# Xplorer_camera.net
KiCad netlist of a schematic drawn in Altium Designer
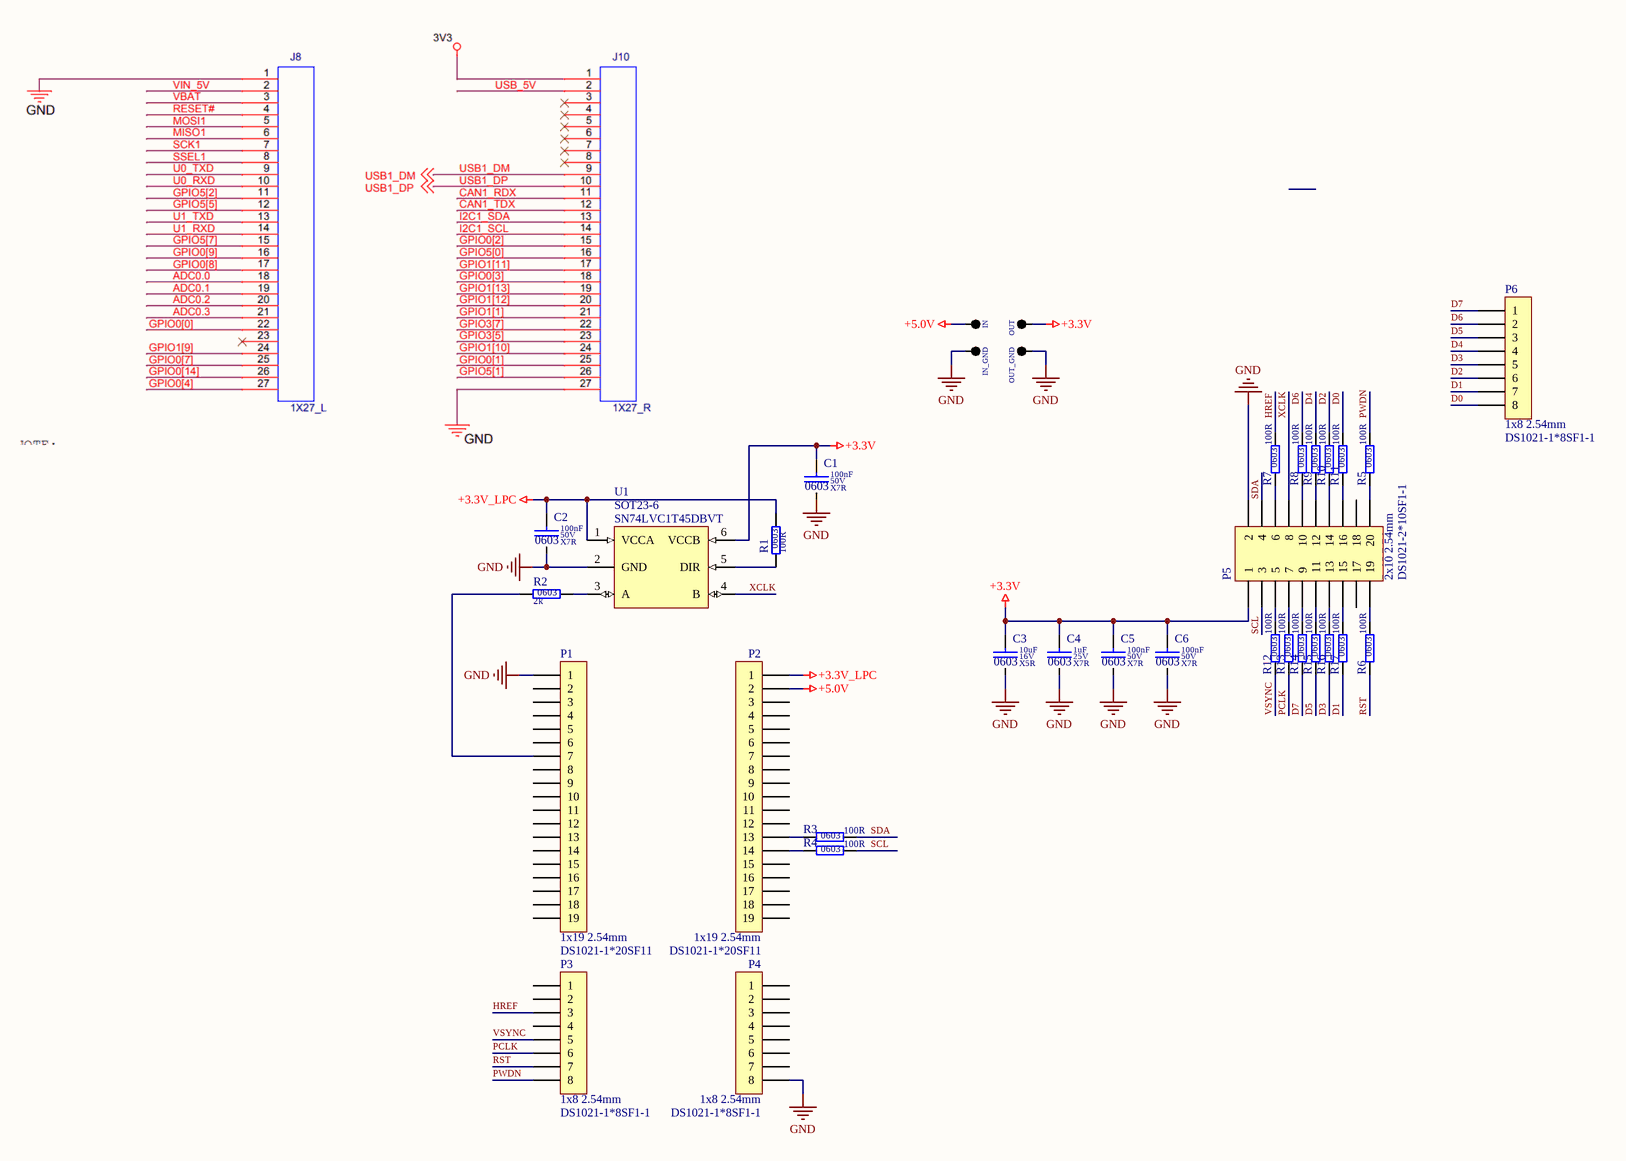
[diagram p0: Xplorer_camera.SchDoc]

(export (version "E")
  (design (tool "Eeschema 10.0.6"))
  (components
    (comp (ref "C1")
      (value "100nF")
      (footprint "C_0603_1608")
      (description "Capacitor")
      (fields
        (field (name "DIELECTRIC") "X7R")
        (field (name "VOLTAGE") "50V")
        (field (name "SCH_FOOTPRINT") "0603")
        (field (name "PART NUMBER") "C_100nF_50V_X7R_0603_5")
        (field (name "MANUFACTURER") "Samsung")
      )
      (libsource (lib "Library") (part "C"))
    )
    (comp (ref "C2")
      (value "100nF")
      (footprint "C_0603_1608")
      (description "Capacitor")
      (fields
        (field (name "DIELECTRIC") "X7R")
        (field (name "VOLTAGE") "50V")
        (field (name "SCH_FOOTPRINT") "0603")
        (field (name "PART NUMBER") "C_100nF_50V_X7R_0603_5")
        (field (name "MANUFACTURER") "Samsung")
      )
      (libsource (lib "Library") (part "C"))
    )
    (comp (ref "C3")
      (value "10uF")
      (footprint "C_0603_1608")
      (description "Capacitor")
      (fields
        (field (name "DIELECTRIC") "X5R")
        (field (name "VOLTAGE") "16V")
        (field (name "SCH_FOOTPRINT") "0603")
        (field (name "PART NUMBER") "C_10uF_16V_X5R_0603_20")
        (field (name "MANUFACTURER") "Samsung Electro-Mechanics")
      )
      (libsource (lib "Library") (part "C"))
    )
    (comp (ref "C4")
      (value "1uF")
      (footprint "C_0603_1608")
      (description "Capacitor")
      (fields
        (field (name "DIELECTRIC") "X7R")
        (field (name "VOLTAGE") "25V")
        (field (name "SCH_FOOTPRINT") "0603")
        (field (name "PART NUMBER") "C_1uF_25V_X7R_0603_10")
        (field (name "MANUFACTURER") "Samsung")
      )
      (libsource (lib "Library") (part "C"))
    )
    (comp (ref "C5")
      (value "100nF")
      (footprint "C_0603_1608")
      (description "Capacitor")
      (fields
        (field (name "DIELECTRIC") "X7R")
        (field (name "VOLTAGE") "50V")
        (field (name "SCH_FOOTPRINT") "0603")
        (field (name "PART NUMBER") "C_100nF_50V_X7R_0603_5")
        (field (name "MANUFACTURER") "Samsung")
      )
      (libsource (lib "Library") (part "C"))
    )
    (comp (ref "C6")
      (value "100nF")
      (footprint "C_0603_1608")
      (description "Capacitor")
      (fields
        (field (name "DIELECTRIC") "X7R")
        (field (name "VOLTAGE") "50V")
        (field (name "SCH_FOOTPRINT") "0603")
        (field (name "PART NUMBER") "C_100nF_50V_X7R_0603_5")
        (field (name "MANUFACTURER") "Samsung")
      )
      (libsource (lib "Library") (part "C"))
    )
    (comp (ref "IN")
      (value "Single pin")
      (footprint "TP_1PIN")
      (description "Testpoint")
      (fields (field (name "PART NUMBER") "TP_1PIN"))
      (libsource (lib "Library") (part "TP_TESTPOINT"))
    )
    (comp (ref "IN_GND")
      (value "Single pin")
      (footprint "TP_1PIN")
      (description "Testpoint")
      (fields (field (name "PART NUMBER") "TP_1PIN"))
      (libsource (lib "Library") (part "TP_TESTPOINT"))
    )
    (comp (ref "OUT")
      (value "Single pin")
      (footprint "TP_1PIN")
      (description "Testpoint")
      (fields (field (name "PART NUMBER") "TP_1PIN"))
      (libsource (lib "Library") (part "TP_TESTPOINT"))
    )
    (comp (ref "OUT_GND")
      (value "Single pin")
      (footprint "TP_1PIN")
      (description "Testpoint")
      (fields (field (name "PART NUMBER") "TP_1PIN"))
      (libsource (lib "Library") (part "TP_TESTPOINT"))
    )
    (comp (ref "P1")
      (value "DS1021-1*20SF11")
      (footprint "P_HEADER_1x19_2.54")
      (description "Pin Header")
      (fields
        (field (name "SCH_FOOTPRINT") "1x19 2.54mm")
        (field (name "PART NUMBER") "P_HEADER_1x19_2.54")
        (field (name "MANUFACTURER") "Connfly")
      )
      (libsource (lib "") (part "P_HEADER_1x19_1"))
    )
    (comp (ref "P2")
      (value "DS1021-1*20SF11")
      (footprint "P_HEADER_1x19_2.54")
      (description "Pin Header")
      (fields
        (field (name "SCH_FOOTPRINT") "1x19 2.54mm")
        (field (name "PART NUMBER") "P_HEADER_1x19_2.54")
        (field (name "MANUFACTURER") "Connfly")
      )
      (libsource (lib "Library") (part "P_HEADER_1x19"))
    )
    (comp (ref "P3")
      (value "DS1021-1*8SF1-1")
      (footprint "P_HEADER_1x8_2.54")
      (description "Pin Header")
      (fields
        (field (name "SCH_FOOTPRINT") "1x8 2.54mm")
        (field (name "PART NUMBER") "P_HEADER_1x8_2.54")
        (field (name "MANUFACTURER") "Connfly")
      )
      (libsource (lib "Library") (part "P_HEADER_1x8"))
    )
    (comp (ref "P4")
      (value "DS1021-1*8SF1-1")
      (footprint "P_HEADER_1x8_2.54")
      (description "Pin Header")
      (fields
        (field (name "SCH_FOOTPRINT") "1x8 2.54mm")
        (field (name "PART NUMBER") "P_HEADER_1x8_2.54")
        (field (name "MANUFACTURER") "Connfly")
      )
      (libsource (lib "") (part "P_HEADER_1x8_1"))
    )
    (comp (ref "P5")
      (value "DS1021-2*10SF1-1")
      (footprint "P_HEADER_2x10_2.54")
      (description "Pin Header")
      (fields
        (field (name "SCH_FOOTPRINT") "2x10 2.54mm")
        (field (name "PART NUMBER") "P_HEADER_2x10_2.54")
        (field (name "MANUFACTURER") "Connfly")
      )
      (libsource (lib "Library") (part "P_HEADER_2x10"))
    )
    (comp (ref "P6")
      (value "DS1021-1*8SF1-1")
      (footprint "P_HEADER_1x8_2.54")
      (description "Pin Header")
      (fields
        (field (name "SCH_FOOTPRINT") "1x8 2.54mm")
        (field (name "PART NUMBER") "P_HEADER_1x8_2.54")
        (field (name "MANUFACTURER") "Connfly")
      )
      (libsource (lib "Library") (part "P_HEADER_1x8"))
    )
    (comp (ref "R1")
      (value "100R")
      (footprint "R_0603_1608")
      (fields
        (field (name "SCH_FOOTPRINT") "0603")
        (field (name "PART NUMBER") "R_100R_0603_1")
        (field (name "VOLTAGE") "50V")
        (field (name "POWER") "100mW")
      )
      (libsource (lib "Library") (part "R"))
    )
    (comp (ref "R2")
      (value "2k")
      (footprint "R_0603_1608")
      (fields
        (field (name "SCH_FOOTPRINT") "0603")
        (field (name "PART NUMBER") "R_2k_0603_1")
        (field (name "VOLTAGE") "50V")
        (field (name "POWER") "100mW")
      )
      (libsource (lib "Library") (part "R"))
    )
    (comp (ref "R3")
      (value "100R")
      (footprint "R_0603_1608")
      (fields
        (field (name "SCH_FOOTPRINT") "0603")
        (field (name "PART NUMBER") "R_100R_0603_1")
        (field (name "VOLTAGE") "50V")
        (field (name "POWER") "100mW")
      )
      (libsource (lib "Library") (part "R"))
    )
    (comp (ref "R4")
      (value "100R")
      (footprint "R_0603_1608")
      (fields
        (field (name "SCH_FOOTPRINT") "0603")
        (field (name "PART NUMBER") "R_100R_0603_1")
        (field (name "VOLTAGE") "50V")
        (field (name "POWER") "100mW")
      )
      (libsource (lib "Library") (part "R"))
    )
    (comp (ref "R5")
      (value "100R")
      (footprint "R_0603_1608")
      (fields
        (field (name "SCH_FOOTPRINT") "0603")
        (field (name "PART NUMBER") "R_100R_0603_1")
        (field (name "VOLTAGE") "50V")
        (field (name "POWER") "100mW")
      )
      (libsource (lib "Library") (part "R"))
    )
    (comp (ref "R6")
      (value "100R")
      (footprint "R_0603_1608")
      (fields
        (field (name "SCH_FOOTPRINT") "0603")
        (field (name "PART NUMBER") "R_100R_0603_1")
        (field (name "VOLTAGE") "50V")
        (field (name "POWER") "100mW")
      )
      (libsource (lib "Library") (part "R"))
    )
    (comp (ref "R7")
      (value "100R")
      (footprint "R_0603_1608")
      (fields
        (field (name "SCH_FOOTPRINT") "0603")
        (field (name "PART NUMBER") "R_100R_0603_1")
        (field (name "VOLTAGE") "50V")
        (field (name "POWER") "100mW")
      )
      (libsource (lib "Library") (part "R"))
    )
    (comp (ref "R8")
      (value "100R")
      (footprint "R_0603_1608")
      (fields
        (field (name "SCH_FOOTPRINT") "0603")
        (field (name "PART NUMBER") "R_100R_0603_1")
        (field (name "VOLTAGE") "50V")
        (field (name "POWER") "100mW")
      )
      (libsource (lib "Library") (part "R"))
    )
    (comp (ref "R9")
      (value "100R")
      (footprint "R_0603_1608")
      (fields
        (field (name "SCH_FOOTPRINT") "0603")
        (field (name "PART NUMBER") "R_100R_0603_1")
        (field (name "VOLTAGE") "50V")
        (field (name "POWER") "100mW")
      )
      (libsource (lib "Library") (part "R"))
    )
    (comp (ref "R10")
      (value "100R")
      (footprint "R_0603_1608")
      (fields
        (field (name "SCH_FOOTPRINT") "0603")
        (field (name "PART NUMBER") "R_100R_0603_1")
        (field (name "VOLTAGE") "50V")
        (field (name "POWER") "100mW")
      )
      (libsource (lib "Library") (part "R"))
    )
    (comp (ref "R11")
      (value "100R")
      (footprint "R_0603_1608")
      (fields
        (field (name "SCH_FOOTPRINT") "0603")
        (field (name "PART NUMBER") "R_100R_0603_1")
        (field (name "VOLTAGE") "50V")
        (field (name "POWER") "100mW")
      )
      (libsource (lib "Library") (part "R"))
    )
    (comp (ref "R12")
      (value "100R")
      (footprint "R_0603_1608")
      (fields
        (field (name "SCH_FOOTPRINT") "0603")
        (field (name "PART NUMBER") "R_100R_0603_1")
        (field (name "VOLTAGE") "50V")
        (field (name "POWER") "100mW")
      )
      (libsource (lib "Library") (part "R"))
    )
    (comp (ref "R13")
      (value "100R")
      (footprint "R_0603_1608")
      (fields
        (field (name "SCH_FOOTPRINT") "0603")
        (field (name "PART NUMBER") "R_100R_0603_1")
        (field (name "VOLTAGE") "50V")
        (field (name "POWER") "100mW")
      )
      (libsource (lib "Library") (part "R"))
    )
    (comp (ref "R14")
      (value "100R")
      (footprint "R_0603_1608")
      (fields
        (field (name "SCH_FOOTPRINT") "0603")
        (field (name "PART NUMBER") "R_100R_0603_1")
        (field (name "VOLTAGE") "50V")
        (field (name "POWER") "100mW")
      )
      (libsource (lib "Library") (part "R"))
    )
    (comp (ref "R15")
      (value "100R")
      (footprint "R_0603_1608")
      (fields
        (field (name "SCH_FOOTPRINT") "0603")
        (field (name "PART NUMBER") "R_100R_0603_1")
        (field (name "VOLTAGE") "50V")
        (field (name "POWER") "100mW")
      )
      (libsource (lib "Library") (part "R"))
    )
    (comp (ref "R16")
      (value "100R")
      (footprint "R_0603_1608")
      (fields
        (field (name "SCH_FOOTPRINT") "0603")
        (field (name "PART NUMBER") "R_100R_0603_1")
        (field (name "VOLTAGE") "50V")
        (field (name "POWER") "100mW")
      )
      (libsource (lib "Library") (part "R"))
    )
    (comp (ref "R17")
      (value "100R")
      (footprint "R_0603_1608")
      (fields
        (field (name "SCH_FOOTPRINT") "0603")
        (field (name "PART NUMBER") "R_100R_0603_1")
        (field (name "VOLTAGE") "50V")
        (field (name "POWER") "100mW")
      )
      (libsource (lib "Library") (part "R"))
    )
    (comp (ref "U1")
      (value "SN74LVC1T45DBVT")
      (footprint "SOT23-6_SC74A_SOT753")
      (fields
        (field (name "SCH_FOOTPRINT") "SOT23-6")
        (field (name "PART NUMBER") "U_SN74LVC1T45DBVT")
        (field (name "MANUFACTURER") "Texas Instruments")
        (field (name "Comment") "Single-Bit Dual-Supply Bus Transceiver")
      )
      (libsource (lib "Library") (part "U_SN74LVC1T45"))
    )
  )
  (nets
    (net (code "1") (name "+3.3V") (class "Default")
      (node (ref "C1") (pin "1") (pinfunction "1_1") (pintype "passive"))
      (node (ref "C3") (pin "1") (pinfunction "1_1") (pintype "passive"))
      (node (ref "C4") (pin "1") (pinfunction "1_1") (pintype "passive"))
      (node (ref "C5") (pin "1") (pinfunction "1_1") (pintype "passive"))
      (node (ref "C6") (pin "1") (pinfunction "1_1") (pintype "passive"))
      (node (ref "OUT") (pin "1") (pinfunction "TP_1") (pintype "passive"))
      (node (ref "P5") (pin "1") (pinfunction "1_1") (pintype "passive"))
      (node (ref "U1") (pin "6") (pinfunction "VCCB_6") (pintype "input"))
    )
    (net (code "2") (name "+3.3V_LPC") (class "Default")
      (node (ref "C2") (pin "1") (pinfunction "1_1") (pintype "passive"))
      (node (ref "P2") (pin "1") (pinfunction "1_1") (pintype "passive"))
      (node (ref "R1") (pin "2") (pinfunction "2_2") (pintype "passive"))
      (node (ref "U1") (pin "1") (pinfunction "VCCA_1") (pintype "input"))
    )
    (net (code "3") (name "+5.0V") (class "Default")
      (node (ref "IN") (pin "1") (pinfunction "TP_1") (pintype "passive"))
      (node (ref "P2") (pin "2") (pinfunction "2_2") (pintype "passive"))
    )
    (net (code "4") (name "/D0") (class "Default")
      (node (ref "P6") (pin "8") (pinfunction "8_8") (pintype "passive"))
      (node (ref "R11") (pin "2") (pinfunction "2_2") (pintype "passive"))
    )
    (net (code "5") (name "/D1") (class "Default")
      (node (ref "P6") (pin "7") (pinfunction "7_7") (pintype "passive"))
      (node (ref "R17") (pin "1") (pinfunction "1_1") (pintype "passive"))
    )
    (net (code "6") (name "/D2") (class "Default")
      (node (ref "P6") (pin "6") (pinfunction "6_6") (pintype "passive"))
      (node (ref "R10") (pin "2") (pinfunction "2_2") (pintype "passive"))
    )
    (net (code "7") (name "/D3") (class "Default")
      (node (ref "P6") (pin "5") (pinfunction "5_5") (pintype "passive"))
      (node (ref "R16") (pin "1") (pinfunction "1_1") (pintype "passive"))
    )
    (net (code "8") (name "/D4") (class "Default")
      (node (ref "P6") (pin "4") (pinfunction "4_4") (pintype "passive"))
      (node (ref "R9") (pin "2") (pinfunction "2_2") (pintype "passive"))
    )
    (net (code "9") (name "/D5") (class "Default")
      (node (ref "P6") (pin "3") (pinfunction "3_3") (pintype "passive"))
      (node (ref "R15") (pin "1") (pinfunction "1_1") (pintype "passive"))
    )
    (net (code "10") (name "/D6") (class "Default")
      (node (ref "P6") (pin "2") (pinfunction "2_2") (pintype "passive"))
      (node (ref "R8") (pin "2") (pinfunction "2_2") (pintype "passive"))
    )
    (net (code "11") (name "/D7") (class "Default")
      (node (ref "P6") (pin "1") (pinfunction "1_1") (pintype "passive"))
      (node (ref "R14") (pin "1") (pinfunction "1_1") (pintype "passive"))
    )
    (net (code "12") (name "/HREF") (class "Default")
      (node (ref "P3") (pin "3") (pinfunction "3_3") (pintype "passive"))
      (node (ref "R7") (pin "2") (pinfunction "2_2") (pintype "passive"))
    )
    (net (code "13") (name "/PCLK") (class "Default")
      (node (ref "P3") (pin "6") (pinfunction "6_6") (pintype "passive"))
      (node (ref "R13") (pin "1") (pinfunction "1_1") (pintype "passive"))
    )
    (net (code "14") (name "/PWDN") (class "Default")
      (node (ref "P3") (pin "8") (pinfunction "8_8") (pintype "passive"))
      (node (ref "R5") (pin "2") (pinfunction "2_2") (pintype "passive"))
    )
    (net (code "15") (name "/RST") (class "Default")
      (node (ref "P3") (pin "7") (pinfunction "7_7") (pintype "passive"))
      (node (ref "R6") (pin "1") (pinfunction "1_1") (pintype "passive"))
    )
    (net (code "16") (name "/SCL") (class "Default")
      (node (ref "P5") (pin "3") (pinfunction "3_3") (pintype "passive"))
      (node (ref "R4") (pin "2") (pinfunction "2_2") (pintype "passive"))
    )
    (net (code "17") (name "/SDA") (class "Default")
      (node (ref "P5") (pin "4") (pinfunction "4_4") (pintype "passive"))
      (node (ref "R3") (pin "2") (pinfunction "2_2") (pintype "passive"))
    )
    (net (code "18") (name "/VSYNC") (class "Default")
      (node (ref "P3") (pin "5") (pinfunction "5_5") (pintype "passive"))
      (node (ref "R12") (pin "1") (pinfunction "1_1") (pintype "passive"))
    )
    (net (code "19") (name "/XCLK") (class "Default")
      (node (ref "P5") (pin "8") (pinfunction "8_8") (pintype "passive"))
      (node (ref "U1") (pin "4") (pinfunction "B_4") (pintype "bidirectional"))
    )
    (net (code "20") (name "GND") (class "Default")
      (node (ref "C1") (pin "2") (pinfunction "2_2") (pintype "passive"))
      (node (ref "C2") (pin "2") (pinfunction "2_2") (pintype "passive"))
      (node (ref "C3") (pin "2") (pinfunction "2_2") (pintype "passive"))
      (node (ref "C4") (pin "2") (pinfunction "2_2") (pintype "passive"))
      (node (ref "C5") (pin "2") (pinfunction "2_2") (pintype "passive"))
      (node (ref "C6") (pin "2") (pinfunction "2_2") (pintype "passive"))
      (node (ref "IN_GND") (pin "1") (pinfunction "TP_1") (pintype "passive"))
      (node (ref "OUT_GND") (pin "1") (pinfunction "TP_1") (pintype "passive"))
      (node (ref "P1") (pin "1") (pinfunction "1_1") (pintype "passive"))
      (node (ref "P4") (pin "8") (pinfunction "8_8") (pintype "passive"))
      (node (ref "P5") (pin "2") (pinfunction "2_2") (pintype "passive"))
      (node (ref "U1") (pin "2") (pinfunction "GND_2") (pintype "power_in"))
    )
    (net (code "21") (name "Net-(P1-Pad7)") (class "Default")
      (node (ref "P1") (pin "7") (pinfunction "7_7") (pintype "passive"))
      (node (ref "R2") (pin "1") (pinfunction "1_1") (pintype "passive"))
    )
    (net (code "22") (name "Net-(P2-Pad13)") (class "Default")
      (node (ref "P2") (pin "13") (pinfunction "13_13") (pintype "passive"))
      (node (ref "R3") (pin "1") (pinfunction "1_1") (pintype "passive"))
    )
    (net (code "23") (name "Net-(P2-Pad14)") (class "Default")
      (node (ref "P2") (pin "14") (pinfunction "14_14") (pintype "passive"))
      (node (ref "R4") (pin "1") (pinfunction "1_1") (pintype "passive"))
    )
    (net (code "24") (name "Net-(P5-Pad5)") (class "Default")
      (node (ref "P5") (pin "5") (pinfunction "5_5") (pintype "passive"))
      (node (ref "R12") (pin "2") (pinfunction "2_2") (pintype "passive"))
    )
    (net (code "25") (name "Net-(P5-Pad6)") (class "Default")
      (node (ref "P5") (pin "6") (pinfunction "6_6") (pintype "passive"))
      (node (ref "R7") (pin "1") (pinfunction "1_1") (pintype "passive"))
    )
    (net (code "26") (name "Net-(P5-Pad7)") (class "Default")
      (node (ref "P5") (pin "7") (pinfunction "7_7") (pintype "passive"))
      (node (ref "R13") (pin "2") (pinfunction "2_2") (pintype "passive"))
    )
    (net (code "27") (name "Net-(P5-Pad9)") (class "Default")
      (node (ref "P5") (pin "9") (pinfunction "9_9") (pintype "passive"))
      (node (ref "R14") (pin "2") (pinfunction "2_2") (pintype "passive"))
    )
    (net (code "28") (name "Net-(P5-Pad10)") (class "Default")
      (node (ref "P5") (pin "10") (pinfunction "10_10") (pintype "passive"))
      (node (ref "R8") (pin "1") (pinfunction "1_1") (pintype "passive"))
    )
    (net (code "29") (name "Net-(P5-Pad11)") (class "Default")
      (node (ref "P5") (pin "11") (pinfunction "11_11") (pintype "passive"))
      (node (ref "R15") (pin "2") (pinfunction "2_2") (pintype "passive"))
    )
    (net (code "30") (name "Net-(P5-Pad12)") (class "Default")
      (node (ref "P5") (pin "12") (pinfunction "12_12") (pintype "passive"))
      (node (ref "R9") (pin "1") (pinfunction "1_1") (pintype "passive"))
    )
    (net (code "31") (name "Net-(P5-Pad13)") (class "Default")
      (node (ref "P5") (pin "13") (pinfunction "13_13") (pintype "passive"))
      (node (ref "R16") (pin "2") (pinfunction "2_2") (pintype "passive"))
    )
    (net (code "32") (name "Net-(P5-Pad14)") (class "Default")
      (node (ref "P5") (pin "14") (pinfunction "14_14") (pintype "passive"))
      (node (ref "R10") (pin "1") (pinfunction "1_1") (pintype "passive"))
    )
    (net (code "33") (name "Net-(P5-Pad15)") (class "Default")
      (node (ref "P5") (pin "15") (pinfunction "15_15") (pintype "passive"))
      (node (ref "R17") (pin "2") (pinfunction "2_2") (pintype "passive"))
    )
    (net (code "34") (name "Net-(P5-Pad16)") (class "Default")
      (node (ref "P5") (pin "16") (pinfunction "16_16") (pintype "passive"))
      (node (ref "R11") (pin "1") (pinfunction "1_1") (pintype "passive"))
    )
    (net (code "35") (name "Net-(P5-Pad19)") (class "Default")
      (node (ref "P5") (pin "19") (pinfunction "19_19") (pintype "passive"))
      (node (ref "R6") (pin "2") (pinfunction "2_2") (pintype "passive"))
    )
    (net (code "36") (name "Net-(P5-Pad20)") (class "Default")
      (node (ref "P5") (pin "20") (pinfunction "20_20") (pintype "passive"))
      (node (ref "R5") (pin "1") (pinfunction "1_1") (pintype "passive"))
    )
    (net (code "37") (name "Net-(U1-A)") (class "Default")
      (node (ref "R2") (pin "2") (pinfunction "2_2") (pintype "passive"))
      (node (ref "U1") (pin "3") (pinfunction "A_3") (pintype "bidirectional"))
    )
    (net (code "38") (name "Net-(U1-DIR)") (class "Default")
      (node (ref "R1") (pin "1") (pinfunction "1_1") (pintype "passive"))
      (node (ref "U1") (pin "5") (pinfunction "DIR_5") (pintype "input"))
    )
    (net (code "39") (name "unconnected-(P1-Pad2)") (class "Default")
      (node (ref "P1") (pin "2") (pinfunction "2_2") (pintype "passive"))
    )
    (net (code "40") (name "unconnected-(P1-Pad3)") (class "Default")
      (node (ref "P1") (pin "3") (pinfunction "3_3") (pintype "passive"))
    )
    (net (code "41") (name "unconnected-(P1-Pad4)") (class "Default")
      (node (ref "P1") (pin "4") (pinfunction "4_4") (pintype "passive"))
    )
    (net (code "42") (name "unconnected-(P1-Pad5)") (class "Default")
      (node (ref "P1") (pin "5") (pinfunction "5_5") (pintype "passive"))
    )
    (net (code "43") (name "unconnected-(P1-Pad6)") (class "Default")
      (node (ref "P1") (pin "6") (pinfunction "6_6") (pintype "passive"))
    )
    (net (code "44") (name "unconnected-(P1-Pad8)") (class "Default")
      (node (ref "P1") (pin "8") (pinfunction "8_8") (pintype "passive"))
    )
    (net (code "45") (name "unconnected-(P1-Pad9)") (class "Default")
      (node (ref "P1") (pin "9") (pinfunction "9_9") (pintype "passive"))
    )
    (net (code "46") (name "unconnected-(P1-Pad10)") (class "Default")
      (node (ref "P1") (pin "10") (pinfunction "10_10") (pintype "passive"))
    )
    (net (code "47") (name "unconnected-(P1-Pad11)") (class "Default")
      (node (ref "P1") (pin "11") (pinfunction "11_11") (pintype "passive"))
    )
    (net (code "48") (name "unconnected-(P1-Pad12)") (class "Default")
      (node (ref "P1") (pin "12") (pinfunction "12_12") (pintype "passive"))
    )
    (net (code "49") (name "unconnected-(P1-Pad13)") (class "Default")
      (node (ref "P1") (pin "13") (pinfunction "13_13") (pintype "passive"))
    )
    (net (code "50") (name "unconnected-(P1-Pad14)") (class "Default")
      (node (ref "P1") (pin "14") (pinfunction "14_14") (pintype "passive"))
    )
    (net (code "51") (name "unconnected-(P1-Pad15)") (class "Default")
      (node (ref "P1") (pin "15") (pinfunction "15_15") (pintype "passive"))
    )
    (net (code "52") (name "unconnected-(P1-Pad16)") (class "Default")
      (node (ref "P1") (pin "16") (pinfunction "16_16") (pintype "passive"))
    )
    (net (code "53") (name "unconnected-(P1-Pad17)") (class "Default")
      (node (ref "P1") (pin "17") (pinfunction "17_17") (pintype "passive"))
    )
    (net (code "54") (name "unconnected-(P1-Pad18)") (class "Default")
      (node (ref "P1") (pin "18") (pinfunction "18_18") (pintype "passive"))
    )
    (net (code "55") (name "unconnected-(P1-Pad19)") (class "Default")
      (node (ref "P1") (pin "19") (pinfunction "19_19") (pintype "passive"))
    )
    (net (code "56") (name "unconnected-(P2-Pad3)") (class "Default")
      (node (ref "P2") (pin "3") (pinfunction "3_3") (pintype "passive"))
    )
    (net (code "57") (name "unconnected-(P2-Pad4)") (class "Default")
      (node (ref "P2") (pin "4") (pinfunction "4_4") (pintype "passive"))
    )
    (net (code "58") (name "unconnected-(P2-Pad5)") (class "Default")
      (node (ref "P2") (pin "5") (pinfunction "5_5") (pintype "passive"))
    )
    (net (code "59") (name "unconnected-(P2-Pad6)") (class "Default")
      (node (ref "P2") (pin "6") (pinfunction "6_6") (pintype "passive"))
    )
    (net (code "60") (name "unconnected-(P2-Pad7)") (class "Default")
      (node (ref "P2") (pin "7") (pinfunction "7_7") (pintype "passive"))
    )
    (net (code "61") (name "unconnected-(P2-Pad8)") (class "Default")
      (node (ref "P2") (pin "8") (pinfunction "8_8") (pintype "passive"))
    )
    (net (code "62") (name "unconnected-(P2-Pad9)") (class "Default")
      (node (ref "P2") (pin "9") (pinfunction "9_9") (pintype "passive"))
    )
    (net (code "63") (name "unconnected-(P2-Pad10)") (class "Default")
      (node (ref "P2") (pin "10") (pinfunction "10_10") (pintype "passive"))
    )
    (net (code "64") (name "unconnected-(P2-Pad11)") (class "Default")
      (node (ref "P2") (pin "11") (pinfunction "11_11") (pintype "passive"))
    )
    (net (code "65") (name "unconnected-(P2-Pad12)") (class "Default")
      (node (ref "P2") (pin "12") (pinfunction "12_12") (pintype "passive"))
    )
    (net (code "66") (name "unconnected-(P2-Pad15)") (class "Default")
      (node (ref "P2") (pin "15") (pinfunction "15_15") (pintype "passive"))
    )
    (net (code "67") (name "unconnected-(P2-Pad16)") (class "Default")
      (node (ref "P2") (pin "16") (pinfunction "16_16") (pintype "passive"))
    )
    (net (code "68") (name "unconnected-(P2-Pad17)") (class "Default")
      (node (ref "P2") (pin "17") (pinfunction "17_17") (pintype "passive"))
    )
    (net (code "69") (name "unconnected-(P2-Pad18)") (class "Default")
      (node (ref "P2") (pin "18") (pinfunction "18_18") (pintype "passive"))
    )
    (net (code "70") (name "unconnected-(P2-Pad19)") (class "Default")
      (node (ref "P2") (pin "19") (pinfunction "19_19") (pintype "passive"))
    )
    (net (code "71") (name "unconnected-(P3-Pad1)") (class "Default")
      (node (ref "P3") (pin "1") (pinfunction "1_1") (pintype "passive"))
    )
    (net (code "72") (name "unconnected-(P3-Pad2)") (class "Default")
      (node (ref "P3") (pin "2") (pinfunction "2_2") (pintype "passive"))
    )
    (net (code "73") (name "unconnected-(P3-Pad4)") (class "Default")
      (node (ref "P3") (pin "4") (pinfunction "4_4") (pintype "passive"))
    )
    (net (code "74") (name "unconnected-(P4-Pad1)") (class "Default")
      (node (ref "P4") (pin "1") (pinfunction "1_1") (pintype "passive"))
    )
    (net (code "75") (name "unconnected-(P4-Pad2)") (class "Default")
      (node (ref "P4") (pin "2") (pinfunction "2_2") (pintype "passive"))
    )
    (net (code "76") (name "unconnected-(P4-Pad3)") (class "Default")
      (node (ref "P4") (pin "3") (pinfunction "3_3") (pintype "passive"))
    )
    (net (code "77") (name "unconnected-(P4-Pad4)") (class "Default")
      (node (ref "P4") (pin "4") (pinfunction "4_4") (pintype "passive"))
    )
    (net (code "78") (name "unconnected-(P4-Pad5)") (class "Default")
      (node (ref "P4") (pin "5") (pinfunction "5_5") (pintype "passive"))
    )
    (net (code "79") (name "unconnected-(P4-Pad6)") (class "Default")
      (node (ref "P4") (pin "6") (pinfunction "6_6") (pintype "passive"))
    )
    (net (code "80") (name "unconnected-(P4-Pad7)") (class "Default")
      (node (ref "P4") (pin "7") (pinfunction "7_7") (pintype "passive"))
    )
    (net (code "81") (name "unconnected-(P5-Pad17)") (class "Default")
      (node (ref "P5") (pin "17") (pinfunction "17_17") (pintype "passive"))
    )
    (net (code "82") (name "unconnected-(P5-Pad18)") (class "Default")
      (node (ref "P5") (pin "18") (pinfunction "18_18") (pintype "passive"))
    )
  )
)
